# DBoard_conn.net
KiCad netlist of a schematic drawn in Altium Designer
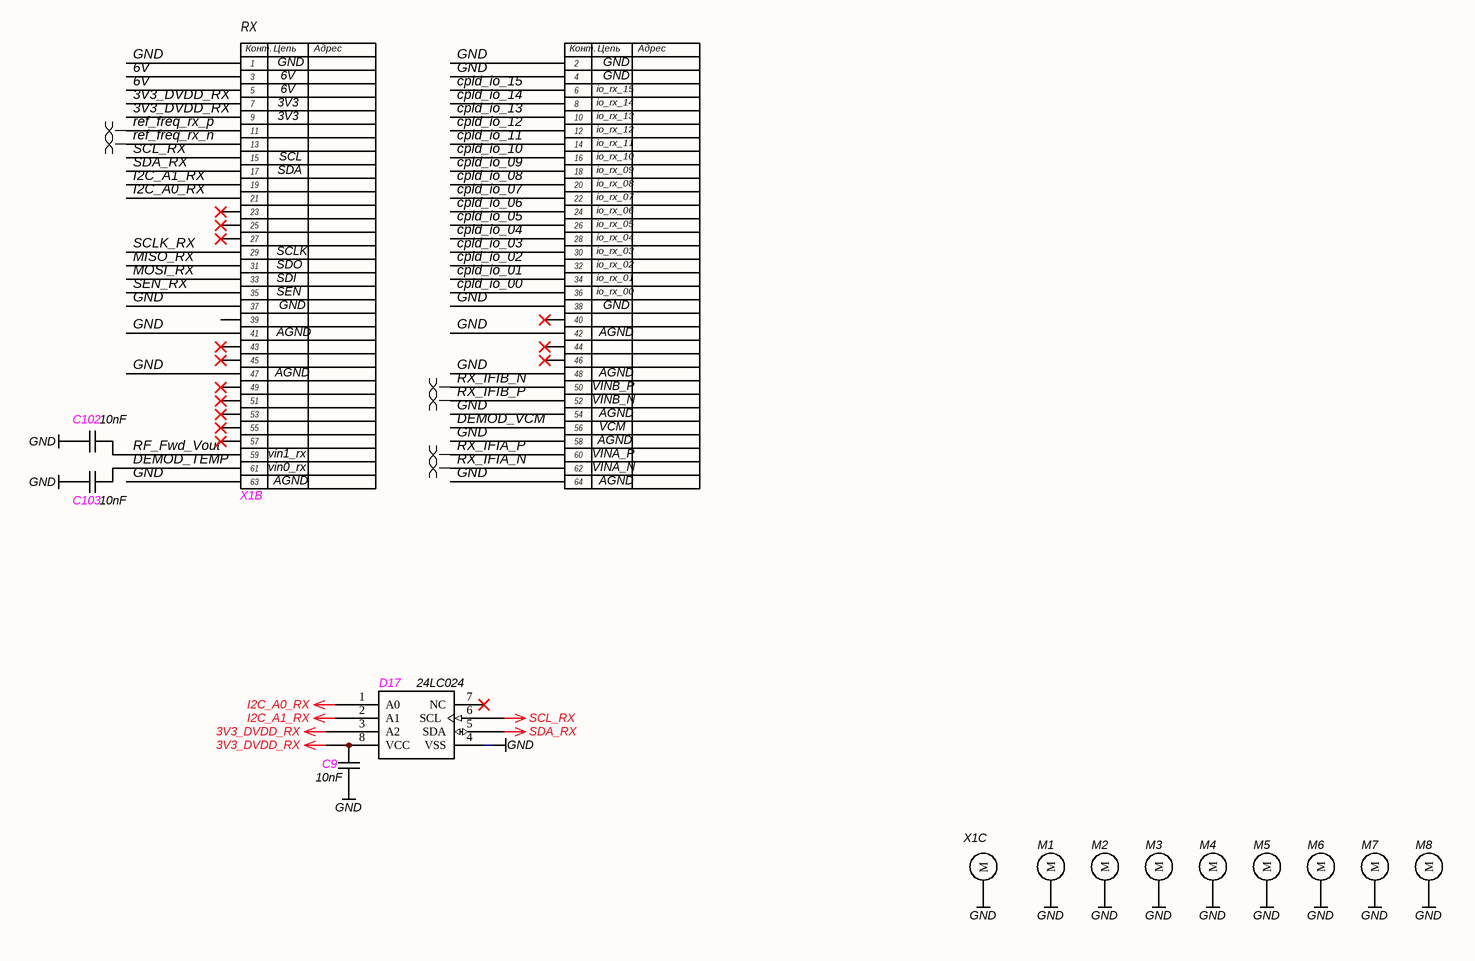
[diagram p0: DBoard_conn.SchDoc]

(export (version "E")
  (design (tool "Eeschema 10.0.6"))
  (components
    (comp (ref "C9")
      (value "10nF")
      (footprint "C0402")
      (description "SMD Capacitor")
      (fields (field (name "MANUFACTURER") "Murata") (field (name "TOLERANCE") "10%"))
      (libsource (lib "Kintex_SDR") (part "CAP"))
    )
    (comp (ref "C102")
      (value "10nF")
      (footprint "C0402")
      (description "SMD Capacitor")
      (fields (field (name "MANUFACTURER") "Murata") (field (name "TOLERANCE") "10%"))
      (libsource (lib "Kintex_SDR") (part "CAP"))
    )
    (comp (ref "C103")
      (value "10nF")
      (footprint "C0402")
      (description "SMD Capacitor")
      (fields (field (name "MANUFACTURER") "Murata") (field (name "TOLERANCE") "10%"))
      (libsource (lib "Kintex_SDR") (part "CAP"))
    )
    (comp (ref "D17")
      (value "24LC024")
      (footprint "SOIC_SN8")
      (description "I2C EEPROM")
      (fields (field (name "MANUFACTURER") "Microchip") (field (name "VOLTAGE") "2.5-5.5V"))
      (libsource (lib "Kintex_SDR") (part "24LC024"))
    )
    (comp (ref "M1")
      (value "Via")
      (footprint "Mechanical_Via_2.6x4.2")
      (description "Mechanical Via")
      (libsource (lib "Kintex_SDR") (part "Mechanical Via"))
    )
    (comp (ref "M2")
      (value "Via")
      (footprint "Mechanical_Via_2.6x4.2")
      (description "Mechanical Via")
      (libsource (lib "Kintex_SDR") (part "Mechanical Via"))
    )
    (comp (ref "M3")
      (value "Via")
      (footprint "Mechanical_Via_2.6x4.2")
      (description "Mechanical Via")
      (libsource (lib "Kintex_SDR") (part "Mechanical Via"))
    )
    (comp (ref "M4")
      (value "Via")
      (footprint "Mechanical_Via_2.6x4.2")
      (description "Mechanical Via")
      (libsource (lib "Kintex_SDR") (part "Mechanical Via"))
    )
    (comp (ref "M5")
      (value "Via")
      (footprint "Mechanical_Via_2.6x4.2")
      (description "Mechanical Via")
      (libsource (lib "Kintex_SDR") (part "Mechanical Via"))
    )
    (comp (ref "M6")
      (value "Via")
      (footprint "Mechanical_Via_2.6x4.2")
      (description "Mechanical Via")
      (libsource (lib "Kintex_SDR") (part "Mechanical Via"))
    )
    (comp (ref "M7")
      (value "Via")
      (footprint "Mechanical_Via_2.6x4.2")
      (description "Mechanical Via")
      (libsource (lib "Kintex_SDR") (part "Mechanical Via"))
    )
    (comp (ref "M8")
      (value "Via")
      (footprint "Mechanical_Via_2.6x4.2")
      (description "Mechanical Via")
      (libsource (lib "Kintex_SDR") (part "Mechanical Via"))
    )
    (comp (ref "X1")
      (value "DBoard")
      (footprint "DBLib:DBoard - half - MB")
      (description "USRP DBoard")
      (fields (field (name "MANUFACTURER") "Molex"))
      (libsource (lib "DBLib") (part "DBoard"))
    )
  )
  (nets
    (net (code "1") (name "/6V") (class "Default")
      (node (ref "X1") (pin "67") (pinfunction "3_67") (pintype "passive"))
      (node (ref "X1") (pin "69") (pinfunction "5_69") (pintype "passive"))
    )
    (net (code "2") (name "/DEMOD_TEMP") (class "Default")
      (node (ref "C103") (pin "2") (pinfunction "2_2") (pintype "passive"))
      (node (ref "X1") (pin "125") (pinfunction "61_125") (pintype "passive"))
    )
    (net (code "3") (name "/DEMOD_VCM") (class "Default")
      (node (ref "X1") (pin "120") (pinfunction "56_120") (pintype "passive"))
    )
    (net (code "4") (name "/MISO_RX") (class "Default")
      (node (ref "X1") (pin "95") (pinfunction "31_95") (pintype "passive"))
    )
    (net (code "5") (name "/MOSI_RX") (class "Default")
      (node (ref "X1") (pin "97") (pinfunction "33_97") (pintype "passive"))
    )
    (net (code "6") (name "/RF_Fwd_Vout") (class "Default")
      (node (ref "C102") (pin "2") (pinfunction "2_2") (pintype "passive"))
      (node (ref "X1") (pin "123") (pinfunction "59_123") (pintype "passive"))
    )
    (net (code "7") (name "/RX_IFIA_N") (class "Default")
      (node (ref "X1") (pin "126") (pinfunction "62_126") (pintype "passive"))
    )
    (net (code "8") (name "/RX_IFIA_P") (class "Default")
      (node (ref "X1") (pin "124") (pinfunction "60_124") (pintype "passive"))
    )
    (net (code "9") (name "/RX_IFIB_N") (class "Default")
      (node (ref "X1") (pin "114") (pinfunction "50_114") (pintype "passive"))
    )
    (net (code "10") (name "/RX_IFIB_P") (class "Default")
      (node (ref "X1") (pin "116") (pinfunction "52_116") (pintype "passive"))
    )
    (net (code "11") (name "/SCLK_RX") (class "Default")
      (node (ref "X1") (pin "93") (pinfunction "29_93") (pintype "passive"))
    )
    (net (code "12") (name "/SEN_RX") (class "Default")
      (node (ref "X1") (pin "99") (pinfunction "35_99") (pintype "passive"))
    )
    (net (code "13") (name "/cpld_io_00") (class "Default")
      (node (ref "X1") (pin "100") (pinfunction "36_100") (pintype "passive"))
    )
    (net (code "14") (name "/cpld_io_01") (class "Default")
      (node (ref "X1") (pin "98") (pinfunction "34_98") (pintype "passive"))
    )
    (net (code "15") (name "/cpld_io_02") (class "Default")
      (node (ref "X1") (pin "96") (pinfunction "32_96") (pintype "passive"))
    )
    (net (code "16") (name "/cpld_io_03") (class "Default")
      (node (ref "X1") (pin "94") (pinfunction "30_94") (pintype "passive"))
    )
    (net (code "17") (name "/cpld_io_04") (class "Default")
      (node (ref "X1") (pin "92") (pinfunction "28_92") (pintype "passive"))
    )
    (net (code "18") (name "/cpld_io_05") (class "Default")
      (node (ref "X1") (pin "90") (pinfunction "26_90") (pintype "passive"))
    )
    (net (code "19") (name "/cpld_io_06") (class "Default")
      (node (ref "X1") (pin "88") (pinfunction "24_88") (pintype "passive"))
    )
    (net (code "20") (name "/cpld_io_07") (class "Default")
      (node (ref "X1") (pin "86") (pinfunction "22_86") (pintype "passive"))
    )
    (net (code "21") (name "/cpld_io_08") (class "Default")
      (node (ref "X1") (pin "84") (pinfunction "20_84") (pintype "passive"))
    )
    (net (code "22") (name "/cpld_io_09") (class "Default")
      (node (ref "X1") (pin "82") (pinfunction "18_82") (pintype "passive"))
    )
    (net (code "23") (name "/cpld_io_10") (class "Default")
      (node (ref "X1") (pin "80") (pinfunction "16_80") (pintype "passive"))
    )
    (net (code "24") (name "/cpld_io_11") (class "Default")
      (node (ref "X1") (pin "78") (pinfunction "14_78") (pintype "passive"))
    )
    (net (code "25") (name "/cpld_io_12") (class "Default")
      (node (ref "X1") (pin "76") (pinfunction "12_76") (pintype "passive"))
    )
    (net (code "26") (name "/cpld_io_13") (class "Default")
      (node (ref "X1") (pin "74") (pinfunction "10_74") (pintype "passive"))
    )
    (net (code "27") (name "/cpld_io_14") (class "Default")
      (node (ref "X1") (pin "72") (pinfunction "8_72") (pintype "passive"))
    )
    (net (code "28") (name "/cpld_io_15") (class "Default")
      (node (ref "X1") (pin "70") (pinfunction "6_70") (pintype "passive"))
    )
    (net (code "29") (name "/ref_freq_rx_n") (class "Default")
      (node (ref "X1") (pin "77") (pinfunction "13_77") (pintype "passive"))
    )
    (net (code "30") (name "/ref_freq_rx_p") (class "Default")
      (node (ref "X1") (pin "75") (pinfunction "11_75") (pintype "passive"))
    )
    (net (code "31") (name "3V3_DVDD_RX") (class "Default")
      (node (ref "C9") (pin "2") (pinfunction "2_2") (pintype "passive"))
      (node (ref "D17") (pin "3") (pinfunction "A2_3") (pintype "passive"))
      (node (ref "D17") (pin "8") (pinfunction "VCC_8") (pintype "power_in"))
      (node (ref "X1") (pin "71") (pinfunction "7_71") (pintype "passive"))
      (node (ref "X1") (pin "73") (pinfunction "9_73") (pintype "passive"))
    )
    (net (code "32") (name "GND") (class "Default")
      (node (ref "C102") (pin "1") (pinfunction "1_1") (pintype "passive"))
      (node (ref "C103") (pin "1") (pinfunction "1_1") (pintype "passive"))
      (node (ref "C9") (pin "1") (pinfunction "1_1") (pintype "passive"))
      (node (ref "D17") (pin "4") (pinfunction "VSS_4") (pintype "power_in"))
      (node (ref "M1") (pin "0") (pinfunction "M_0") (pintype "passive"))
      (node (ref "M2") (pin "0") (pinfunction "M_0") (pintype "passive"))
      (node (ref "M3") (pin "0") (pinfunction "M_0") (pintype "passive"))
      (node (ref "M4") (pin "0") (pinfunction "M_0") (pintype "passive"))
      (node (ref "M5") (pin "0") (pinfunction "M_0") (pintype "passive"))
      (node (ref "M6") (pin "0") (pinfunction "M_0") (pintype "passive"))
      (node (ref "M7") (pin "0") (pinfunction "M_0") (pintype "passive"))
      (node (ref "M8") (pin "0") (pinfunction "M_0") (pintype "passive"))
      (node (ref "X1") (pin "0") (pinfunction "M_0") (pintype "passive"))
      (node (ref "X1") (pin "101") (pinfunction "37_101") (pintype "passive"))
      (node (ref "X1") (pin "102") (pinfunction "38_102") (pintype "passive"))
      (node (ref "X1") (pin "105") (pinfunction "41_105") (pintype "passive"))
      (node (ref "X1") (pin "106") (pinfunction "42_106") (pintype "passive"))
      (node (ref "X1") (pin "111") (pinfunction "47_111") (pintype "passive"))
      (node (ref "X1") (pin "112") (pinfunction "48_112") (pintype "passive"))
      (node (ref "X1") (pin "118") (pinfunction "54_118") (pintype "passive"))
      (node (ref "X1") (pin "122") (pinfunction "58_122") (pintype "passive"))
      (node (ref "X1") (pin "127") (pinfunction "63_127") (pintype "passive"))
      (node (ref "X1") (pin "128") (pinfunction "64_128") (pintype "passive"))
      (node (ref "X1") (pin "65") (pinfunction "1_65") (pintype "passive"))
      (node (ref "X1") (pin "66") (pinfunction "2_66") (pintype "passive"))
      (node (ref "X1") (pin "68") (pinfunction "4_68") (pintype "passive"))
    )
    (net (code "33") (name "I2C_A0_RX") (class "Default")
      (node (ref "D17") (pin "1") (pinfunction "A0_1") (pintype "passive"))
      (node (ref "X1") (pin "85") (pinfunction "21_85") (pintype "passive"))
    )
    (net (code "34") (name "I2C_A1_RX") (class "Default")
      (node (ref "D17") (pin "2") (pinfunction "A1_2") (pintype "passive"))
      (node (ref "X1") (pin "83") (pinfunction "19_83") (pintype "passive"))
    )
    (net (code "35") (name "SCL_RX") (class "Default")
      (node (ref "D17") (pin "6") (pinfunction "SCL_6") (pintype "input"))
      (node (ref "X1") (pin "79") (pinfunction "15_79") (pintype "passive"))
    )
    (net (code "36") (name "SDA_RX") (class "Default")
      (node (ref "D17") (pin "5") (pinfunction "SDA_5") (pintype "bidirectional"))
      (node (ref "X1") (pin "81") (pinfunction "17_81") (pintype "passive"))
    )
    (net (code "37") (name "unconnected-(D17-NC-Pad7)") (class "Default")
      (node (ref "D17") (pin "7") (pinfunction "NC_7") (pintype "passive+no_connect"))
    )
    (net (code "38") (name "unconnected-(X1B-23-Pad87)") (class "Default")
      (node (ref "X1") (pin "87") (pinfunction "23_87") (pintype "passive+no_connect"))
    )
    (net (code "39") (name "unconnected-(X1B-25-Pad89)") (class "Default")
      (node (ref "X1") (pin "89") (pinfunction "25_89") (pintype "passive+no_connect"))
    )
    (net (code "40") (name "unconnected-(X1B-27-Pad91)") (class "Default")
      (node (ref "X1") (pin "91") (pinfunction "27_91") (pintype "passive+no_connect"))
    )
    (net (code "41") (name "unconnected-(X1B-39-Pad103)") (class "Default")
      (node (ref "X1") (pin "103") (pinfunction "39_103") (pintype "passive"))
    )
    (net (code "42") (name "unconnected-(X1B-40-Pad104)") (class "Default")
      (node (ref "X1") (pin "104") (pinfunction "40_104") (pintype "passive+no_connect"))
    )
    (net (code "43") (name "unconnected-(X1B-43-Pad107)") (class "Default")
      (node (ref "X1") (pin "107") (pinfunction "43_107") (pintype "passive+no_connect"))
    )
    (net (code "44") (name "unconnected-(X1B-44-Pad108)") (class "Default")
      (node (ref "X1") (pin "108") (pinfunction "44_108") (pintype "passive+no_connect"))
    )
    (net (code "45") (name "unconnected-(X1B-45-Pad109)") (class "Default")
      (node (ref "X1") (pin "109") (pinfunction "45_109") (pintype "passive+no_connect"))
    )
    (net (code "46") (name "unconnected-(X1B-46-Pad110)") (class "Default")
      (node (ref "X1") (pin "110") (pinfunction "46_110") (pintype "passive+no_connect"))
    )
    (net (code "47") (name "unconnected-(X1B-49-Pad113)") (class "Default")
      (node (ref "X1") (pin "113") (pinfunction "49_113") (pintype "passive+no_connect"))
    )
    (net (code "48") (name "unconnected-(X1B-51-Pad115)") (class "Default")
      (node (ref "X1") (pin "115") (pinfunction "51_115") (pintype "passive+no_connect"))
    )
    (net (code "49") (name "unconnected-(X1B-53-Pad117)") (class "Default")
      (node (ref "X1") (pin "117") (pinfunction "53_117") (pintype "passive+no_connect"))
    )
    (net (code "50") (name "unconnected-(X1B-55-Pad119)") (class "Default")
      (node (ref "X1") (pin "119") (pinfunction "55_119") (pintype "passive+no_connect"))
    )
    (net (code "51") (name "unconnected-(X1B-57-Pad121)") (class "Default")
      (node (ref "X1") (pin "121") (pinfunction "57_121") (pintype "passive+no_connect"))
    )
  )
)
